# LedRing.net
KiCad netlist of a schematic drawn in EAGLE
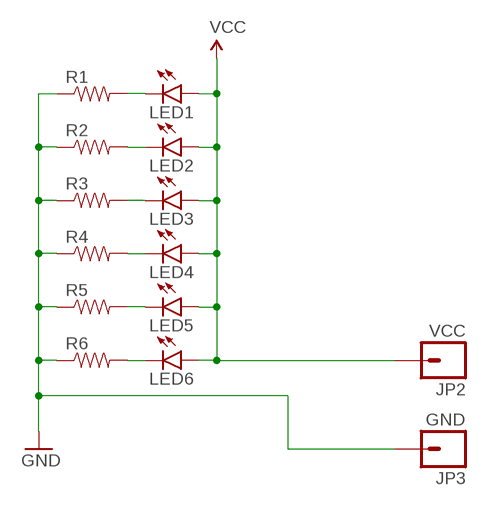
[diagram p0: schematic, sheet 1]

(export (version "E")
  (design (tool "Eeschema 10.0.6"))
  (components
    (comp (ref "JP2")
      (value "VCC")
      (footprint "eagle-import:1X01NS-KIT")
      (libsource (lib "eagle-import") (part "M01NOSILK-KIT"))
    )
    (comp (ref "JP3")
      (value "GND")
      (footprint "eagle-import:1X01NS-KIT")
      (libsource (lib "eagle-import") (part "M01NOSILK-KIT"))
    )
    (comp (ref "LED1")
      (value "LED1206")
      (footprint "eagle-import:LED-1206")
      (libsource (lib "eagle-import") (part "LED1206"))
    )
    (comp (ref "LED2")
      (value "LED1206")
      (footprint "eagle-import:LED-1206")
      (libsource (lib "eagle-import") (part "LED1206"))
    )
    (comp (ref "LED3")
      (value "LED1206")
      (footprint "eagle-import:LED-1206")
      (libsource (lib "eagle-import") (part "LED1206"))
    )
    (comp (ref "LED4")
      (value "LED1206")
      (footprint "eagle-import:LED-1206")
      (libsource (lib "eagle-import") (part "LED1206"))
    )
    (comp (ref "LED5")
      (value "LED1206")
      (footprint "eagle-import:LED-1206")
      (libsource (lib "eagle-import") (part "LED1206"))
    )
    (comp (ref "LED6")
      (value "LED1206")
      (footprint "eagle-import:LED-1206")
      (libsource (lib "eagle-import") (part "LED1206"))
    )
    (comp (ref "R1")
      (value "RESISTOR1206")
      (footprint "eagle-import:1206")
      (libsource (lib "eagle-import") (part "RESISTOR1206"))
    )
    (comp (ref "R2")
      (value "RESISTOR1206")
      (footprint "eagle-import:1206")
      (libsource (lib "eagle-import") (part "RESISTOR1206"))
    )
    (comp (ref "R3")
      (value "RESISTOR1206")
      (footprint "eagle-import:1206")
      (libsource (lib "eagle-import") (part "RESISTOR1206"))
    )
    (comp (ref "R4")
      (value "RESISTOR1206")
      (footprint "eagle-import:1206")
      (libsource (lib "eagle-import") (part "RESISTOR1206"))
    )
    (comp (ref "R5")
      (value "RESISTOR1206")
      (footprint "eagle-import:1206")
      (libsource (lib "eagle-import") (part "RESISTOR1206"))
    )
    (comp (ref "R6")
      (value "RESISTOR1206")
      (footprint "eagle-import:1206")
      (libsource (lib "eagle-import") (part "RESISTOR1206"))
    )
  )
  (nets
    (net (code "1") (name "GND") (class "Default")
      (node (ref "JP3") (pin "1") (pinfunction "1_1") (pintype "passive"))
      (node (ref "R1") (pin "1") (pinfunction "1_1") (pintype "passive"))
      (node (ref "R2") (pin "1") (pinfunction "1_1") (pintype "passive"))
      (node (ref "R3") (pin "1") (pinfunction "1_1") (pintype "passive"))
      (node (ref "R4") (pin "1") (pinfunction "1_1") (pintype "passive"))
      (node (ref "R5") (pin "1") (pinfunction "1_1") (pintype "passive"))
      (node (ref "R6") (pin "1") (pinfunction "1_1") (pintype "passive"))
    )
    (net (code "2") (name "Net-(LED1-PadC)") (class "Default")
      (node (ref "LED1") (pin "C") (pinfunction "C_C") (pintype "passive"))
      (node (ref "R1") (pin "2") (pinfunction "2_2") (pintype "passive"))
    )
    (net (code "3") (name "Net-(LED2-PadC)") (class "Default")
      (node (ref "LED2") (pin "C") (pinfunction "C_C") (pintype "passive"))
      (node (ref "R2") (pin "2") (pinfunction "2_2") (pintype "passive"))
    )
    (net (code "4") (name "Net-(LED3-PadC)") (class "Default")
      (node (ref "LED3") (pin "C") (pinfunction "C_C") (pintype "passive"))
      (node (ref "R3") (pin "2") (pinfunction "2_2") (pintype "passive"))
    )
    (net (code "5") (name "Net-(LED4-PadC)") (class "Default")
      (node (ref "LED4") (pin "C") (pinfunction "C_C") (pintype "passive"))
      (node (ref "R4") (pin "2") (pinfunction "2_2") (pintype "passive"))
    )
    (net (code "6") (name "Net-(LED5-PadC)") (class "Default")
      (node (ref "LED5") (pin "C") (pinfunction "C_C") (pintype "passive"))
      (node (ref "R5") (pin "2") (pinfunction "2_2") (pintype "passive"))
    )
    (net (code "7") (name "Net-(LED6-PadC)") (class "Default")
      (node (ref "LED6") (pin "C") (pinfunction "C_C") (pintype "passive"))
      (node (ref "R6") (pin "2") (pinfunction "2_2") (pintype "passive"))
    )
    (net (code "8") (name "VCC") (class "Default")
      (node (ref "JP2") (pin "1") (pinfunction "1_1") (pintype "passive"))
      (node (ref "LED1") (pin "A") (pinfunction "A_A") (pintype "passive"))
      (node (ref "LED2") (pin "A") (pinfunction "A_A") (pintype "passive"))
      (node (ref "LED3") (pin "A") (pinfunction "A_A") (pintype "passive"))
      (node (ref "LED4") (pin "A") (pinfunction "A_A") (pintype "passive"))
      (node (ref "LED5") (pin "A") (pinfunction "A_A") (pintype "passive"))
      (node (ref "LED6") (pin "A") (pinfunction "A_A") (pintype "passive"))
    )
  )
)
